# Sheet1.net
KiCad netlist of a schematic drawn in Altium Designer
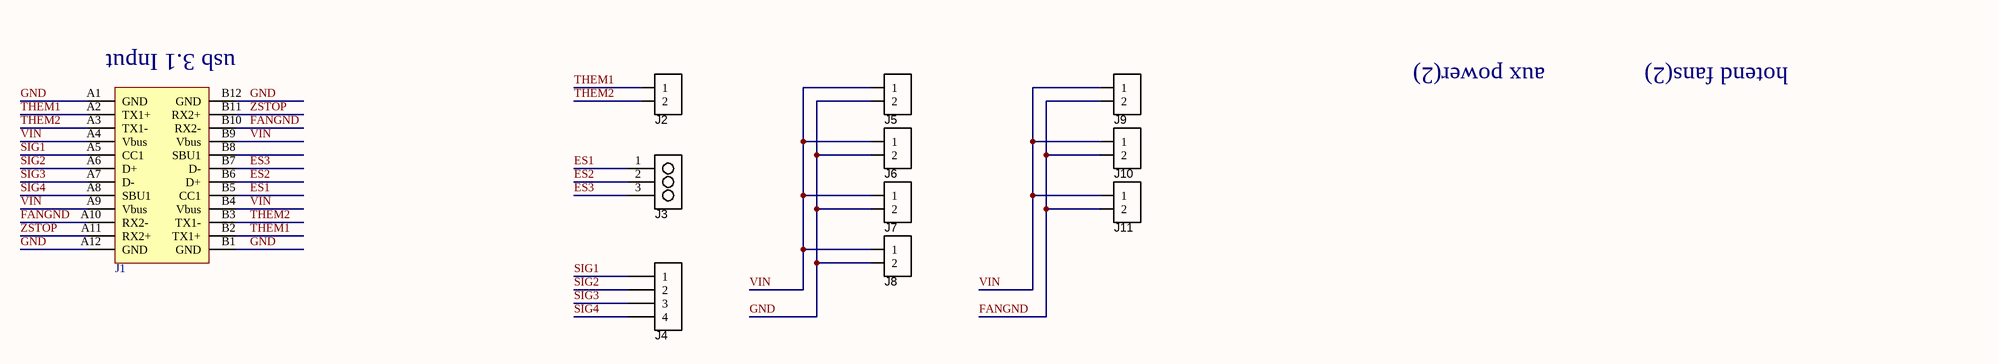
[diagram p0: Sheet1.SchDoc]

(export (version "E")
  (design (tool "Eeschema 10.0.6"))
  (components
    (comp (ref "J1")
      (value "USB_3_1")
      (footprint "USB_3.1")
      (description "USB 3.1 Connector")
      (fields
        (field (name "MANUFACTURER") "Amphenol Commercial Products")
        (field (name "MANUFACTURER PART NUMBER") "12401548E4#2A")
      )
      (libsource (lib "Schlib2") (part "USB 3.1"))
    )
    (comp (ref "J2")
      (value "Connector, jumper")
      (footprint "JMP2_RA")
      (description "Connector Header 0.100in Right-angle single row")
      (libsource (lib "PBL - Connectors") (part "CONN_JMP_RA"))
    )
    (comp (ref "J3")
      (value "CONN_SOCKET_1x3P_0.100in")
      (footprint "1x3POS_SOCKET_LOWPROF")
      (description "Socket header THT 3-Pos Low profile Single-row 2.54mm pitch")
      (libsource (lib "PBL - Connectors") (part "CONN_SOCKET_1x3P_0.100in"))
    )
    (comp (ref "J4")
      (value "~")
      (footprint "HDR1X4_2.54MMP")
      (description "Header 4-pin")
      (libsource (lib "PBL - Connectors") (part "Header4P"))
    )
    (comp (ref "J5")
      (value "Connector, jumper")
      (footprint "JMP2_RA")
      (description "Connector Header 0.100in Right-angle single row")
      (libsource (lib "PBL - Connectors") (part "CONN_JMP_RA"))
    )
    (comp (ref "J6")
      (value "Connector, jumper")
      (footprint "JMP2_RA")
      (description "Connector Header 0.100in Right-angle single row")
      (libsource (lib "PBL - Connectors") (part "CONN_JMP_RA"))
    )
    (comp (ref "J7")
      (value "Connector, jumper")
      (footprint "JMP2_RA")
      (description "Connector Header 0.100in Right-angle single row")
      (libsource (lib "PBL - Connectors") (part "CONN_JMP_RA"))
    )
    (comp (ref "J8")
      (value "Connector, jumper")
      (footprint "JMP2_RA")
      (description "Connector Header 0.100in Right-angle single row")
      (libsource (lib "PBL - Connectors") (part "CONN_JMP_RA"))
    )
    (comp (ref "J9")
      (value "Connector, jumper")
      (footprint "JMP2_RA")
      (description "Connector Header 0.100in Right-angle single row")
      (libsource (lib "PBL - Connectors") (part "CONN_JMP_RA"))
    )
    (comp (ref "J10")
      (value "Connector, jumper")
      (footprint "JMP2_RA")
      (description "Connector Header 0.100in Right-angle single row")
      (libsource (lib "PBL - Connectors") (part "CONN_JMP_RA"))
    )
    (comp (ref "J11")
      (value "Connector, jumper")
      (footprint "JMP2_RA")
      (description "Connector Header 0.100in Right-angle single row")
      (libsource (lib "PBL - Connectors") (part "CONN_JMP_RA"))
    )
  )
  (nets
    (net (code "1") (name "/ES1") (class "Default")
      (node (ref "J1") (pin "B5") (pinfunction "CC1_B5") (pintype "passive"))
      (node (ref "J3") (pin "1") (pinfunction "1_1") (pintype "passive"))
    )
    (net (code "2") (name "/ES2") (class "Default")
      (node (ref "J1") (pin "B6") (pinfunction "D+_B6") (pintype "passive"))
      (node (ref "J3") (pin "2") (pinfunction "2_2") (pintype "passive"))
    )
    (net (code "3") (name "/ES3") (class "Default")
      (node (ref "J1") (pin "B7") (pinfunction "D-_B7") (pintype "passive"))
      (node (ref "J3") (pin "3") (pinfunction "3_3") (pintype "passive"))
    )
    (net (code "4") (name "/FANGND") (class "Default")
      (node (ref "J1") (pin "A10") (pinfunction "RX2-_A10") (pintype "passive"))
      (node (ref "J1") (pin "B10") (pinfunction "RX2-_B10") (pintype "passive"))
      (node (ref "J10") (pin "2") (pinfunction "2_2") (pintype "passive"))
      (node (ref "J11") (pin "2") (pinfunction "2_2") (pintype "passive"))
      (node (ref "J9") (pin "2") (pinfunction "2_2") (pintype "passive"))
    )
    (net (code "5") (name "/GND") (class "Default")
      (node (ref "J1") (pin "A1") (pinfunction "GND_A1") (pintype "passive"))
      (node (ref "J1") (pin "A12") (pinfunction "GND_A12") (pintype "passive"))
      (node (ref "J1") (pin "B1") (pinfunction "GND_B1") (pintype "passive"))
      (node (ref "J1") (pin "B12") (pinfunction "GND_B12") (pintype "passive"))
      (node (ref "J5") (pin "2") (pinfunction "2_2") (pintype "passive"))
      (node (ref "J6") (pin "2") (pinfunction "2_2") (pintype "passive"))
      (node (ref "J7") (pin "2") (pinfunction "2_2") (pintype "passive"))
      (node (ref "J8") (pin "2") (pinfunction "2_2") (pintype "passive"))
    )
    (net (code "6") (name "/SIG1") (class "Default")
      (node (ref "J1") (pin "A5") (pinfunction "CC1_A5") (pintype "passive"))
      (node (ref "J4") (pin "1") (pinfunction "1_1") (pintype "passive"))
    )
    (net (code "7") (name "/SIG2") (class "Default")
      (node (ref "J1") (pin "A6") (pinfunction "D+_A6") (pintype "passive"))
      (node (ref "J4") (pin "2") (pinfunction "2_2") (pintype "passive"))
    )
    (net (code "8") (name "/SIG3") (class "Default")
      (node (ref "J1") (pin "A7") (pinfunction "D-_A7") (pintype "passive"))
      (node (ref "J4") (pin "3") (pinfunction "3_3") (pintype "passive"))
    )
    (net (code "9") (name "/SIG4") (class "Default")
      (node (ref "J1") (pin "A8") (pinfunction "SBU1_A8") (pintype "passive"))
      (node (ref "J4") (pin "4") (pinfunction "4_4") (pintype "passive"))
    )
    (net (code "10") (name "/THEM1") (class "Default")
      (node (ref "J1") (pin "A2") (pinfunction "TX1+_A2") (pintype "passive"))
      (node (ref "J1") (pin "B2") (pinfunction "TX1+_B2") (pintype "passive"))
      (node (ref "J2") (pin "1") (pinfunction "1_1") (pintype "passive"))
    )
    (net (code "11") (name "/THEM2") (class "Default")
      (node (ref "J1") (pin "A3") (pinfunction "TX1-_A3") (pintype "passive"))
      (node (ref "J1") (pin "B3") (pinfunction "TX1-_B3") (pintype "passive"))
      (node (ref "J2") (pin "2") (pinfunction "2_2") (pintype "passive"))
    )
    (net (code "12") (name "/VIN") (class "Default")
      (node (ref "J1") (pin "A4") (pinfunction "Vbus_A4") (pintype "passive"))
      (node (ref "J1") (pin "A9") (pinfunction "Vbus_A9") (pintype "passive"))
      (node (ref "J1") (pin "B4") (pinfunction "Vbus_B4") (pintype "passive"))
      (node (ref "J1") (pin "B9") (pinfunction "Vbus_B9") (pintype "passive"))
      (node (ref "J10") (pin "1") (pinfunction "1_1") (pintype "passive"))
      (node (ref "J11") (pin "1") (pinfunction "1_1") (pintype "passive"))
      (node (ref "J5") (pin "1") (pinfunction "1_1") (pintype "passive"))
      (node (ref "J6") (pin "1") (pinfunction "1_1") (pintype "passive"))
      (node (ref "J7") (pin "1") (pinfunction "1_1") (pintype "passive"))
      (node (ref "J8") (pin "1") (pinfunction "1_1") (pintype "passive"))
      (node (ref "J9") (pin "1") (pinfunction "1_1") (pintype "passive"))
    )
    (net (code "13") (name "/ZSTOP") (class "Default")
      (node (ref "J1") (pin "A11") (pinfunction "RX2+_A11") (pintype "passive"))
      (node (ref "J1") (pin "B11") (pinfunction "RX2+_B11") (pintype "passive"))
    )
    (net (code "14") (name "unconnected-(J1-SBU1-PadB8)") (class "Default")
      (node (ref "J1") (pin "B8") (pinfunction "SBU1_B8") (pintype "passive"))
    )
  )
)
